# Peripheral.net
KiCad netlist of a schematic drawn in Altium Designer
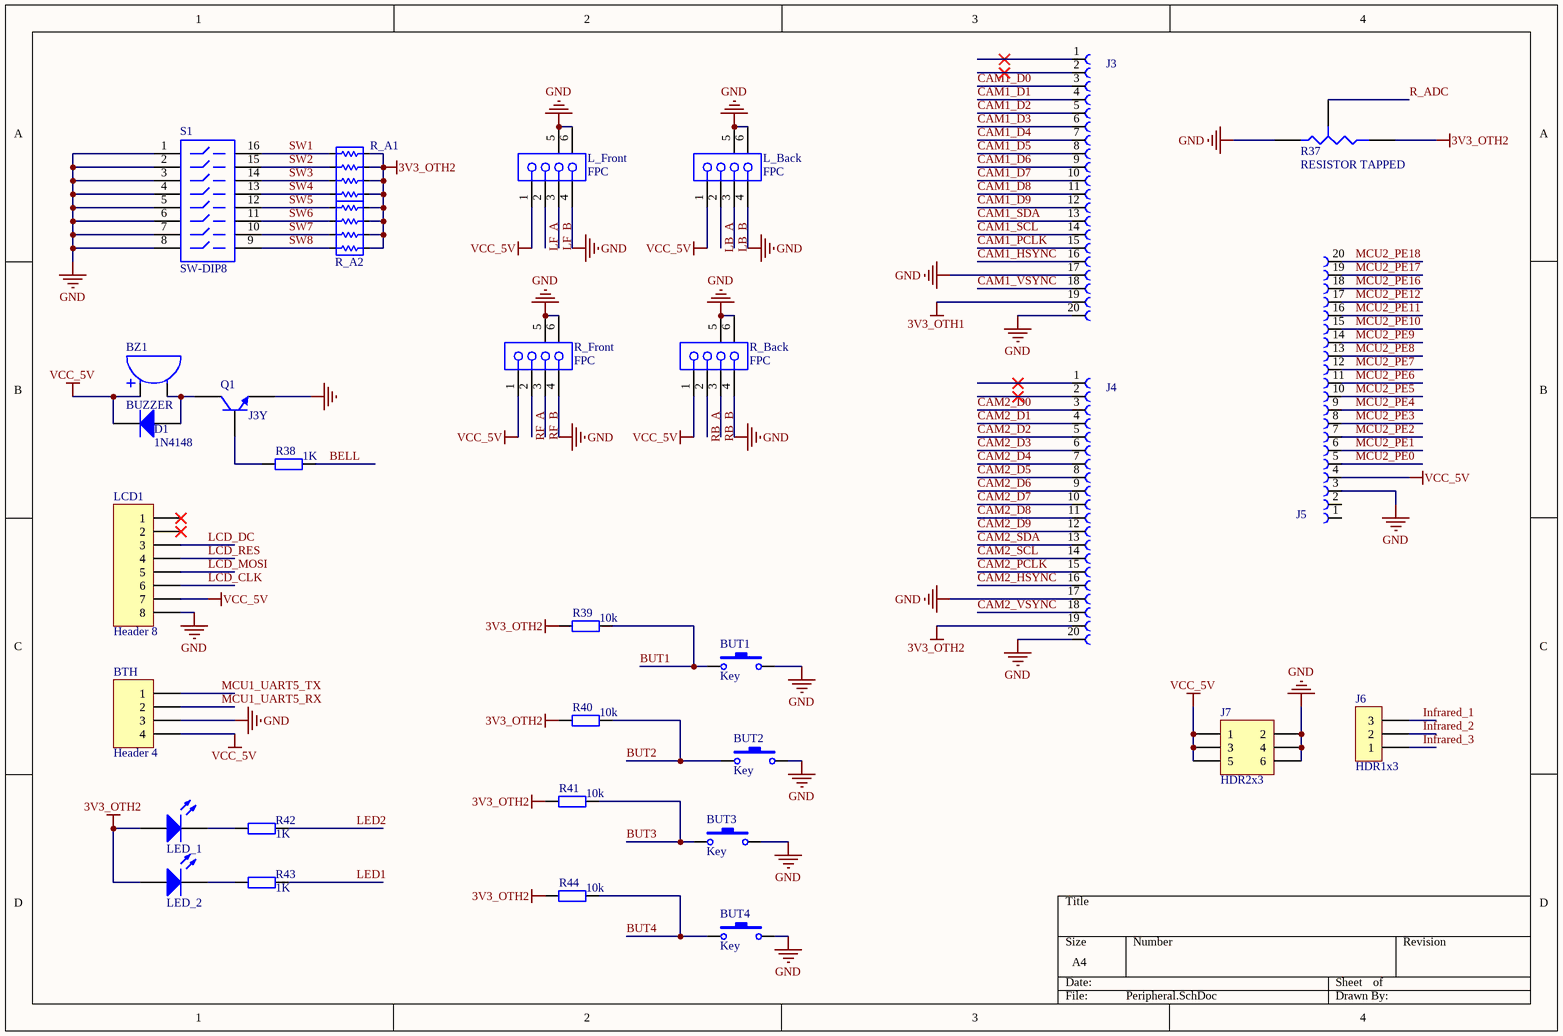
[diagram p0: Peripheral.SchDoc]

(export (version "E")
  (design (tool "Eeschema 10.0.6"))
  (components
    (comp (ref "BTH")
      (value "Header 4")
      (footprint "HDR1X4")
      (description "Header, 4-Pin")
      (fields (field (name "PUBLISHER") "Altium Limited"))
      (libsource (lib "K60_main board") (part "Header 4"))
    )
    (comp (ref "BUT1") (value "Key") (footprint "Key_PB") (libsource (lib "MKV58") (part "KEY")))
    (comp (ref "BUT2") (value "Key") (footprint "Key_PB") (libsource (lib "MKV58") (part "KEY")))
    (comp (ref "BUT3") (value "Key") (footprint "Key_PB") (libsource (lib "MKV58") (part "KEY")))
    (comp (ref "BUT4") (value "Key") (footprint "Key_PB") (libsource (lib "MKV58") (part "KEY")))
    (comp (ref "BZ1")
      (value "BUZZER")
      (footprint "BUZZER-D12.0X8.5-6.5-0.8")
      (description "Buzzer")
      (libsource (lib "MyLib") (part "BUZZER"))
    )
    (comp (ref "D1")
      (value "1N4148")
      (footprint "1N4148")
      (fields (field (name "PUBLISHER") "Altium Limited"))
      (libsource (lib "YMYPcbLib") (part "Diode"))
    )
    (comp (ref "J3")
      (value "~")
      (footprint "*68712014522")
      (description "WR-FPC 0.5mm ZIF Connector Bottom 20pin")
      (fields (field (name "MF") "Wurth Electronics") (field (name "MP") "68712014522"))
      (libsource (lib "MyLib") (part "FPC-0.5-20"))
    )
    (comp (ref "J4")
      (value "~")
      (footprint "*68712014522")
      (description "WR-FPC 0.5mm ZIF Connector Bottom 20pin")
      (fields (field (name "MF") "Wurth Electronics") (field (name "MP") "68712014522"))
      (libsource (lib "MyLib") (part "FPC-0.5-20"))
    )
    (comp (ref "J5")
      (value "68712014522")
      (footprint "*68712014522")
      (description "WR-FPC 0.5mm ZIF Connector Bottom 20pin")
      (fields (field (name "MF") "Wurth Electronics"))
      (libsource (lib "MyLib") (part "FPC-0.5-20"))
    )
    (comp (ref "J6")
      (value "HDR1x3")
      (footprint "PIN-3-2.54-1.0")
      (description "Connector")
      (libsource (lib "MyLib") (part "HDR1x3"))
    )
    (comp (ref "J7")
      (value "HDR2x3")
      (footprint "PIN-2x3-2.54-1.0")
      (description "Connector")
      (libsource (lib "MyLib") (part "HDR2x3"))
    )
    (comp (ref "LCD1")
      (value "Header 8")
      (footprint "HDR1X8")
      (description "Header, 8-Pin")
      (fields (field (name "PUBLISHER") "Altium Limited"))
      (libsource (lib "K60_main board") (part "Header 8"))
    )
    (comp (ref "LED_1") (value "LED") (footprint "LED") (libsource (lib "xunpianzhen") (part "LED")))
    (comp (ref "LED_2") (value "LED") (footprint "LED") (libsource (lib "xunpianzhen") (part "LED")))
    (comp (ref "L_Back")
      (value "FPC")
      (footprint "FH12-10(4)SA-1SH")
      (description "FH12 Series, \"Flip-Lock\" SMT/ZIF Connector - 1.0mm Spaced Bottom Eccentric Contact")
      (fields (field (name "PUBLISHER") "Altium Limited"))
      (libsource (lib "stub") (part "CL586-0537-0"))
    )
    (comp (ref "L_Front")
      (value "FPC")
      (footprint "FH12-10(4)SA-1SH")
      (description "FH12 Series, \"Flip-Lock\" SMT/ZIF Connector - 1.0mm Spaced Bottom Eccentric Contact")
      (fields (field (name "PUBLISHER") "Altium Limited"))
      (libsource (lib "stub") (part "CL586-0537-0"))
    )
    (comp (ref "Q1")
      (value "J3Y")
      (footprint "SOT23")
      (description "NPN Bipolar Transistor")
      (fields (field (name "PUBLISHER") "Altium Limited"))
      (libsource (lib "KL26_main board") (part "NPN"))
    )
    (comp (ref "R37")
      (value "RESISTOR TAPPED")
      (footprint "0932电位器")
      (libsource (lib "MyLib") (part "RESISTOR TAPPED"))
    )
    (comp (ref "R38")
      (value "1K")
      (footprint "0805")
      (description "Resistor")
      (fields (field (name "PUBLISHER") "Altium Limited"))
      (libsource (lib "Miscellaneous Devices") (part "Res2"))
    )
    (comp (ref "R39")
      (value "10k")
      (footprint "0805")
      (description "Resistor")
      (fields (field (name "Comment") "Res2") (field (name "PUBLISHER") "Altium Limited"))
      (libsource (lib "Miscellaneous Devices") (part "Res2"))
    )
    (comp (ref "R40")
      (value "10k")
      (footprint "0805")
      (description "Resistor")
      (fields (field (name "Comment") "Res2") (field (name "PUBLISHER") "Altium Limited"))
      (libsource (lib "Miscellaneous Devices") (part "Res2"))
    )
    (comp (ref "R41")
      (value "10k")
      (footprint "0805")
      (description "Resistor")
      (fields (field (name "Comment") "Res2") (field (name "PUBLISHER") "Altium Limited"))
      (libsource (lib "Miscellaneous Devices") (part "Res2"))
    )
    (comp (ref "R42")
      (value "1K")
      (footprint "0805")
      (description "Resistor")
      (fields (field (name "Comment") "Res2") (field (name "PUBLISHER") "Altium Limited"))
      (libsource (lib "Miscellaneous Devices") (part "Res2"))
    )
    (comp (ref "R43")
      (value "1K")
      (footprint "0805")
      (description "Resistor")
      (fields (field (name "Comment") "Res2") (field (name "PUBLISHER") "Altium Limited"))
      (libsource (lib "Miscellaneous Devices") (part "Res2"))
    )
    (comp (ref "R44")
      (value "10k")
      (footprint "0805")
      (description "Resistor")
      (fields (field (name "Comment") "Res2") (field (name "PUBLISHER") "Altium Limited"))
      (libsource (lib "Miscellaneous Devices") (part "Res2"))
    )
    (comp (ref "R_A1") (value "Res Array") (footprint "R_Array") (libsource (lib "MyLib") (part "R_Array")))
    (comp (ref "R_A2")
      (value "Resistor Array")
      (footprint "Res Array")
      (description "Resistor")
      (fields (field (name "PUBLISHER") "Altium Limited"))
      (libsource (lib "MyLib") (part "Res_Array_4"))
    )
    (comp (ref "R_Back")
      (value "FPC")
      (footprint "FH12-10(4)SA-1SH")
      (description "FH12 Series, \"Flip-Lock\" SMT/ZIF Connector - 1.0mm Spaced Bottom Eccentric Contact")
      (fields (field (name "PUBLISHER") "Altium Limited"))
      (libsource (lib "stub") (part "CL586-0537-0"))
    )
    (comp (ref "R_Front")
      (value "FPC")
      (footprint "FH12-10(4)SA-1SH")
      (description "FH12 Series, \"Flip-Lock\" SMT/ZIF Connector - 1.0mm Spaced Bottom Eccentric Contact")
      (fields (field (name "PUBLISHER") "Altium Limited"))
      (libsource (lib "stub") (part "CL586-0537-0"))
    )
    (comp (ref "S1")
      (value "SW-DIP8")
      (footprint "DIP-16-KEY")
      (description "4009 Series DIP Switch, Raised actuator")
      (fields (field (name "PUBLISHER") "Altium Limited"))
      (libsource (lib "Miscellaneous Devices") (part "SW-DIP8"))
    )
  )
  (nets
    (net (code "1") (name "/BELL") (class "Default")
      (node (ref "R38") (pin "2") (pinfunction "2_2") (pintype "passive"))
    )
    (net (code "2") (name "/BUT1") (class "Default")
      (node (ref "BUT1") (pin "1") (pinfunction "1_1") (pintype "passive"))
      (node (ref "R39") (pin "2") (pinfunction "2_2") (pintype "passive"))
    )
    (net (code "3") (name "/BUT2") (class "Default")
      (node (ref "BUT2") (pin "1") (pinfunction "1_1") (pintype "passive"))
      (node (ref "R40") (pin "2") (pinfunction "2_2") (pintype "passive"))
    )
    (net (code "4") (name "/BUT3") (class "Default")
      (node (ref "BUT3") (pin "1") (pinfunction "1_1") (pintype "passive"))
      (node (ref "R41") (pin "2") (pinfunction "2_2") (pintype "passive"))
    )
    (net (code "5") (name "/BUT4") (class "Default")
      (node (ref "BUT4") (pin "1") (pinfunction "1_1") (pintype "passive"))
      (node (ref "R44") (pin "2") (pinfunction "2_2") (pintype "passive"))
    )
    (net (code "6") (name "/CAM1_D0") (class "Default")
      (node (ref "J3") (pin "3") (pinfunction "3_3") (pintype "passive"))
    )
    (net (code "7") (name "/CAM1_D1") (class "Default")
      (node (ref "J3") (pin "4") (pinfunction "4_4") (pintype "passive"))
    )
    (net (code "8") (name "/CAM1_D2") (class "Default")
      (node (ref "J3") (pin "5") (pinfunction "5_5") (pintype "passive"))
    )
    (net (code "9") (name "/CAM1_D3") (class "Default")
      (node (ref "J3") (pin "6") (pinfunction "6_6") (pintype "passive"))
    )
    (net (code "10") (name "/CAM1_D4") (class "Default")
      (node (ref "J3") (pin "7") (pinfunction "7_7") (pintype "passive"))
    )
    (net (code "11") (name "/CAM1_D5") (class "Default")
      (node (ref "J3") (pin "8") (pinfunction "8_8") (pintype "passive"))
    )
    (net (code "12") (name "/CAM1_D6") (class "Default")
      (node (ref "J3") (pin "9") (pinfunction "9_9") (pintype "passive"))
    )
    (net (code "13") (name "/CAM1_D7") (class "Default")
      (node (ref "J3") (pin "10") (pinfunction "10_10") (pintype "passive"))
    )
    (net (code "14") (name "/CAM1_D8") (class "Default")
      (node (ref "J3") (pin "11") (pinfunction "11_11") (pintype "passive"))
    )
    (net (code "15") (name "/CAM1_D9") (class "Default")
      (node (ref "J3") (pin "12") (pinfunction "12_12") (pintype "passive"))
    )
    (net (code "16") (name "/CAM1_HSYNC") (class "Default")
      (node (ref "J3") (pin "16") (pinfunction "16_16") (pintype "passive"))
    )
    (net (code "17") (name "/CAM1_PCLK") (class "Default")
      (node (ref "J3") (pin "15") (pinfunction "15_15") (pintype "passive"))
    )
    (net (code "18") (name "/CAM1_SCL") (class "Default")
      (node (ref "J3") (pin "14") (pinfunction "14_14") (pintype "passive"))
    )
    (net (code "19") (name "/CAM1_SDA") (class "Default")
      (node (ref "J3") (pin "13") (pinfunction "13_13") (pintype "passive"))
    )
    (net (code "20") (name "/CAM1_VSYNC") (class "Default")
      (node (ref "J3") (pin "18") (pinfunction "18_18") (pintype "passive"))
    )
    (net (code "21") (name "/CAM2_D0") (class "Default")
      (node (ref "J4") (pin "3") (pinfunction "3_3") (pintype "passive"))
    )
    (net (code "22") (name "/CAM2_D1") (class "Default")
      (node (ref "J4") (pin "4") (pinfunction "4_4") (pintype "passive"))
    )
    (net (code "23") (name "/CAM2_D2") (class "Default")
      (node (ref "J4") (pin "5") (pinfunction "5_5") (pintype "passive"))
    )
    (net (code "24") (name "/CAM2_D3") (class "Default")
      (node (ref "J4") (pin "6") (pinfunction "6_6") (pintype "passive"))
    )
    (net (code "25") (name "/CAM2_D4") (class "Default")
      (node (ref "J4") (pin "7") (pinfunction "7_7") (pintype "passive"))
    )
    (net (code "26") (name "/CAM2_D5") (class "Default")
      (node (ref "J4") (pin "8") (pinfunction "8_8") (pintype "passive"))
    )
    (net (code "27") (name "/CAM2_D6") (class "Default")
      (node (ref "J4") (pin "9") (pinfunction "9_9") (pintype "passive"))
    )
    (net (code "28") (name "/CAM2_D7") (class "Default")
      (node (ref "J4") (pin "10") (pinfunction "10_10") (pintype "passive"))
    )
    (net (code "29") (name "/CAM2_D8") (class "Default")
      (node (ref "J4") (pin "11") (pinfunction "11_11") (pintype "passive"))
    )
    (net (code "30") (name "/CAM2_D9") (class "Default")
      (node (ref "J4") (pin "12") (pinfunction "12_12") (pintype "passive"))
    )
    (net (code "31") (name "/CAM2_HSYNC") (class "Default")
      (node (ref "J4") (pin "16") (pinfunction "16_16") (pintype "passive"))
    )
    (net (code "32") (name "/CAM2_PCLK") (class "Default")
      (node (ref "J4") (pin "15") (pinfunction "15_15") (pintype "passive"))
    )
    (net (code "33") (name "/CAM2_SCL") (class "Default")
      (node (ref "J4") (pin "14") (pinfunction "14_14") (pintype "passive"))
    )
    (net (code "34") (name "/CAM2_SDA") (class "Default")
      (node (ref "J4") (pin "13") (pinfunction "13_13") (pintype "passive"))
    )
    (net (code "35") (name "/CAM2_VSYNC") (class "Default")
      (node (ref "J4") (pin "18") (pinfunction "18_18") (pintype "passive"))
    )
    (net (code "36") (name "/Infrared_1") (class "Default")
      (node (ref "J6") (pin "3") (pinfunction "3_3") (pintype "passive"))
    )
    (net (code "37") (name "/Infrared_2") (class "Default")
      (node (ref "J6") (pin "2") (pinfunction "2_2") (pintype "passive"))
    )
    (net (code "38") (name "/Infrared_3") (class "Default")
      (node (ref "J6") (pin "1") (pinfunction "1_1") (pintype "passive"))
    )
    (net (code "39") (name "/LB_A") (class "Default")
      (node (ref "L_Back") (pin "2") (pinfunction "2_2") (pintype "passive"))
    )
    (net (code "40") (name "/LB_B") (class "Default")
      (node (ref "L_Back") (pin "3") (pinfunction "3_3") (pintype "passive"))
    )
    (net (code "41") (name "/LCD_CLK") (class "Default")
      (node (ref "LCD1") (pin "6") (pinfunction "6_6") (pintype "passive"))
    )
    (net (code "42") (name "/LCD_DC") (class "Default")
      (node (ref "LCD1") (pin "3") (pinfunction "3_3") (pintype "passive"))
    )
    (net (code "43") (name "/LCD_MOSI") (class "Default")
      (node (ref "LCD1") (pin "5") (pinfunction "5_5") (pintype "passive"))
    )
    (net (code "44") (name "/LCD_RES") (class "Default")
      (node (ref "LCD1") (pin "4") (pinfunction "4_4") (pintype "passive"))
    )
    (net (code "45") (name "/LED1") (class "Default")
      (node (ref "R43") (pin "2") (pinfunction "2_2") (pintype "passive"))
    )
    (net (code "46") (name "/LED2") (class "Default")
      (node (ref "R42") (pin "2") (pinfunction "2_2") (pintype "passive"))
    )
    (net (code "47") (name "/LF_A") (class "Default")
      (node (ref "L_Front") (pin "2") (pinfunction "2_2") (pintype "passive"))
    )
    (net (code "48") (name "/LF_B") (class "Default")
      (node (ref "L_Front") (pin "3") (pinfunction "3_3") (pintype "passive"))
    )
    (net (code "49") (name "/MCU1_UART5_RX") (class "Default")
      (node (ref "BTH") (pin "2") (pinfunction "2_2") (pintype "passive"))
    )
    (net (code "50") (name "/MCU1_UART5_TX") (class "Default")
      (node (ref "BTH") (pin "1") (pinfunction "1_1") (pintype "passive"))
    )
    (net (code "51") (name "/MCU2_PE0") (class "Default")
      (node (ref "J5") (pin "5") (pinfunction "5_5") (pintype "passive"))
    )
    (net (code "52") (name "/MCU2_PE1") (class "Default")
      (node (ref "J5") (pin "6") (pinfunction "6_6") (pintype "passive"))
    )
    (net (code "53") (name "/MCU2_PE2") (class "Default")
      (node (ref "J5") (pin "7") (pinfunction "7_7") (pintype "passive"))
    )
    (net (code "54") (name "/MCU2_PE3") (class "Default")
      (node (ref "J5") (pin "8") (pinfunction "8_8") (pintype "passive"))
    )
    (net (code "55") (name "/MCU2_PE4") (class "Default")
      (node (ref "J5") (pin "9") (pinfunction "9_9") (pintype "passive"))
    )
    (net (code "56") (name "/MCU2_PE5") (class "Default")
      (node (ref "J5") (pin "10") (pinfunction "10_10") (pintype "passive"))
    )
    (net (code "57") (name "/MCU2_PE6") (class "Default")
      (node (ref "J5") (pin "11") (pinfunction "11_11") (pintype "passive"))
    )
    (net (code "58") (name "/MCU2_PE7") (class "Default")
      (node (ref "J5") (pin "12") (pinfunction "12_12") (pintype "passive"))
    )
    (net (code "59") (name "/MCU2_PE8") (class "Default")
      (node (ref "J5") (pin "13") (pinfunction "13_13") (pintype "passive"))
    )
    (net (code "60") (name "/MCU2_PE9") (class "Default")
      (node (ref "J5") (pin "14") (pinfunction "14_14") (pintype "passive"))
    )
    (net (code "61") (name "/MCU2_PE10") (class "Default")
      (node (ref "J5") (pin "15") (pinfunction "15_15") (pintype "passive"))
    )
    (net (code "62") (name "/MCU2_PE11") (class "Default")
      (node (ref "J5") (pin "16") (pinfunction "16_16") (pintype "passive"))
    )
    (net (code "63") (name "/MCU2_PE12") (class "Default")
      (node (ref "J5") (pin "17") (pinfunction "17_17") (pintype "passive"))
    )
    (net (code "64") (name "/MCU2_PE16") (class "Default")
      (node (ref "J5") (pin "18") (pinfunction "18_18") (pintype "passive"))
    )
    (net (code "65") (name "/MCU2_PE17") (class "Default")
      (node (ref "J5") (pin "19") (pinfunction "19_19") (pintype "passive"))
    )
    (net (code "66") (name "/MCU2_PE18") (class "Default")
      (node (ref "J5") (pin "20") (pinfunction "20_20") (pintype "passive"))
    )
    (net (code "67") (name "/RB_A") (class "Default")
      (node (ref "R_Back") (pin "2") (pinfunction "2_2") (pintype "passive"))
    )
    (net (code "68") (name "/RB_B") (class "Default")
      (node (ref "R_Back") (pin "3") (pinfunction "3_3") (pintype "passive"))
    )
    (net (code "69") (name "/RF_A") (class "Default")
      (node (ref "R_Front") (pin "2") (pinfunction "2_2") (pintype "passive"))
    )
    (net (code "70") (name "/RF_B") (class "Default")
      (node (ref "R_Front") (pin "3") (pinfunction "3_3") (pintype "passive"))
    )
    (net (code "71") (name "/R_ADC") (class "Default")
      (node (ref "R37") (pin "3") (pinfunction "TAP_3") (pintype "passive"))
    )
    (net (code "72") (name "/SW1") (class "Default")
      (node (ref "R_A1") (pin "1") (pinfunction "1_1") (pintype "passive"))
      (node (ref "S1") (pin "16") (pinfunction "16_16") (pintype "passive"))
    )
    (net (code "73") (name "/SW2") (class "Default")
      (node (ref "R_A1") (pin "2") (pinfunction "2_2") (pintype "passive"))
      (node (ref "S1") (pin "15") (pinfunction "15_15") (pintype "passive"))
    )
    (net (code "74") (name "/SW3") (class "Default")
      (node (ref "R_A1") (pin "3") (pinfunction "3_3") (pintype "passive"))
      (node (ref "S1") (pin "14") (pinfunction "14_14") (pintype "passive"))
    )
    (net (code "75") (name "/SW4") (class "Default")
      (node (ref "R_A1") (pin "4") (pinfunction "4_4") (pintype "passive"))
      (node (ref "S1") (pin "13") (pinfunction "13_13") (pintype "passive"))
    )
    (net (code "76") (name "/SW5") (class "Default")
      (node (ref "R_A2") (pin "1") (pinfunction "1_1") (pintype "passive"))
      (node (ref "S1") (pin "12") (pinfunction "12_12") (pintype "passive"))
    )
    (net (code "77") (name "/SW6") (class "Default")
      (node (ref "R_A2") (pin "2") (pinfunction "2_2") (pintype "passive"))
      (node (ref "S1") (pin "11") (pinfunction "11_11") (pintype "passive"))
    )
    (net (code "78") (name "/SW7") (class "Default")
      (node (ref "R_A2") (pin "3") (pinfunction "3_3") (pintype "passive"))
      (node (ref "S1") (pin "10") (pinfunction "10_10") (pintype "passive"))
    )
    (net (code "79") (name "/SW8") (class "Default")
      (node (ref "R_A2") (pin "4") (pinfunction "4_4") (pintype "passive"))
      (node (ref "S1") (pin "9") (pinfunction "9_9") (pintype "passive"))
    )
    (net (code "80") (name "3V3_OTH1") (class "Default")
      (node (ref "J3") (pin "19") (pinfunction "19_19") (pintype "passive"))
    )
    (net (code "81") (name "3V3_OTH2") (class "Default")
      (node (ref "J4") (pin "19") (pinfunction "19_19") (pintype "passive"))
      (node (ref "LED_1") (pin "1") (pinfunction "A_1") (pintype "passive"))
      (node (ref "LED_2") (pin "1") (pinfunction "A_1") (pintype "passive"))
      (node (ref "R37") (pin "2") (pinfunction "B_2") (pintype "passive"))
      (node (ref "R39") (pin "1") (pinfunction "1_1") (pintype "passive"))
      (node (ref "R40") (pin "1") (pinfunction "1_1") (pintype "passive"))
      (node (ref "R41") (pin "1") (pinfunction "1_1") (pintype "passive"))
      (node (ref "R44") (pin "1") (pinfunction "1_1") (pintype "passive"))
      (node (ref "R_A1") (pin "5") (pinfunction "5_5") (pintype "passive"))
      (node (ref "R_A1") (pin "6") (pinfunction "6_6") (pintype "passive"))
      (node (ref "R_A1") (pin "7") (pinfunction "7_7") (pintype "passive"))
      (node (ref "R_A1") (pin "8") (pinfunction "8_8") (pintype "passive"))
      (node (ref "R_A2") (pin "5") (pinfunction "5_5") (pintype "passive"))
      (node (ref "R_A2") (pin "6") (pinfunction "6_6") (pintype "passive"))
      (node (ref "R_A2") (pin "7") (pinfunction "7_7") (pintype "passive"))
      (node (ref "R_A2") (pin "8") (pinfunction "8_8") (pintype "passive"))
    )
    (net (code "82") (name "GND") (class "Default")
      (node (ref "BTH") (pin "3") (pinfunction "3_3") (pintype "passive"))
      (node (ref "BUT1") (pin "2") (pinfunction "2_2") (pintype "passive"))
      (node (ref "BUT2") (pin "2") (pinfunction "2_2") (pintype "passive"))
      (node (ref "BUT3") (pin "2") (pinfunction "2_2") (pintype "passive"))
      (node (ref "BUT4") (pin "2") (pinfunction "2_2") (pintype "passive"))
      (node (ref "J3") (pin "17") (pinfunction "17_17") (pintype "passive"))
      (node (ref "J3") (pin "20") (pinfunction "20_20") (pintype "passive"))
      (node (ref "J4") (pin "17") (pinfunction "17_17") (pintype "passive"))
      (node (ref "J4") (pin "20") (pinfunction "20_20") (pintype "passive"))
      (node (ref "J5") (pin "3") (pinfunction "3_3") (pintype "passive"))
      (node (ref "J7") (pin "2") (pinfunction "2_2") (pintype "passive"))
      (node (ref "J7") (pin "4") (pinfunction "4_4") (pintype "passive"))
      (node (ref "J7") (pin "6") (pinfunction "6_6") (pintype "passive"))
      (node (ref "LCD1") (pin "8") (pinfunction "8_8") (pintype "passive"))
      (node (ref "L_Back") (pin "4") (pinfunction "4_4") (pintype "passive"))
      (node (ref "L_Back") (pin "5") (pinfunction "MH1_5") (pintype "passive"))
      (node (ref "L_Back") (pin "6") (pinfunction "MH2_6") (pintype "passive"))
      (node (ref "L_Front") (pin "4") (pinfunction "4_4") (pintype "passive"))
      (node (ref "L_Front") (pin "5") (pinfunction "MH1_5") (pintype "passive"))
      (node (ref "L_Front") (pin "6") (pinfunction "MH2_6") (pintype "passive"))
      (node (ref "Q1") (pin "3") (pinfunction "E_3") (pintype "passive"))
      (node (ref "R37") (pin "1") (pinfunction "A_1") (pintype "passive"))
      (node (ref "R_Back") (pin "4") (pinfunction "4_4") (pintype "passive"))
      (node (ref "R_Back") (pin "5") (pinfunction "MH1_5") (pintype "passive"))
      (node (ref "R_Back") (pin "6") (pinfunction "MH2_6") (pintype "passive"))
      (node (ref "R_Front") (pin "4") (pinfunction "4_4") (pintype "passive"))
      (node (ref "R_Front") (pin "5") (pinfunction "MH1_5") (pintype "passive"))
      (node (ref "R_Front") (pin "6") (pinfunction "MH2_6") (pintype "passive"))
      (node (ref "S1") (pin "1") (pinfunction "1_1") (pintype "passive"))
      (node (ref "S1") (pin "2") (pinfunction "2_2") (pintype "passive"))
      (node (ref "S1") (pin "3") (pinfunction "3_3") (pintype "passive"))
      (node (ref "S1") (pin "4") (pinfunction "4_4") (pintype "passive"))
      (node (ref "S1") (pin "5") (pinfunction "5_5") (pintype "passive"))
      (node (ref "S1") (pin "6") (pinfunction "6_6") (pintype "passive"))
      (node (ref "S1") (pin "7") (pinfunction "7_7") (pintype "passive"))
      (node (ref "S1") (pin "8") (pinfunction "8_8") (pintype "passive"))
    )
    (net (code "83") (name "Net-(D1-A)") (class "Default")
      (node (ref "BZ1") (pin "2") (pinfunction "2_2") (pintype "passive"))
      (node (ref "D1") (pin "1") (pinfunction "A_1") (pintype "passive"))
      (node (ref "Q1") (pin "1") (pinfunction "C_1") (pintype "passive"))
    )
    (net (code "84") (name "Net-(LED_1-K)") (class "Default")
      (node (ref "LED_1") (pin "2") (pinfunction "K_2") (pintype "passive"))
      (node (ref "R42") (pin "1") (pinfunction "1_1") (pintype "passive"))
    )
    (net (code "85") (name "Net-(LED_2-K)") (class "Default")
      (node (ref "LED_2") (pin "2") (pinfunction "K_2") (pintype "passive"))
      (node (ref "R43") (pin "1") (pinfunction "1_1") (pintype "passive"))
    )
    (net (code "86") (name "Net-(Q1-B)") (class "Default")
      (node (ref "Q1") (pin "2") (pinfunction "B_2") (pintype "passive"))
      (node (ref "R38") (pin "1") (pinfunction "1_1") (pintype "passive"))
    )
    (net (code "87") (name "VCC_5V") (class "Default")
      (node (ref "BTH") (pin "4") (pinfunction "4_4") (pintype "passive"))
      (node (ref "BZ1") (pin "1") (pinfunction "1_1") (pintype "passive"))
      (node (ref "D1") (pin "2") (pinfunction "K_2") (pintype "passive"))
      (node (ref "J5") (pin "4") (pinfunction "4_4") (pintype "passive"))
      (node (ref "J7") (pin "1") (pinfunction "1_1") (pintype "passive"))
      (node (ref "J7") (pin "3") (pinfunction "3_3") (pintype "passive"))
      (node (ref "J7") (pin "5") (pinfunction "5_5") (pintype "passive"))
      (node (ref "LCD1") (pin "7") (pinfunction "7_7") (pintype "passive"))
      (node (ref "L_Back") (pin "1") (pinfunction "1_1") (pintype "passive"))
      (node (ref "L_Front") (pin "1") (pinfunction "1_1") (pintype "passive"))
      (node (ref "R_Back") (pin "1") (pinfunction "1_1") (pintype "passive"))
      (node (ref "R_Front") (pin "1") (pinfunction "1_1") (pintype "passive"))
    )
    (net (code "88") (name "unconnected-(J3-Pad1)") (class "Default")
      (node (ref "J3") (pin "1") (pinfunction "1_1") (pintype "passive"))
    )
    (net (code "89") (name "unconnected-(J3-Pad2)") (class "Default")
      (node (ref "J3") (pin "2") (pinfunction "2_2") (pintype "passive"))
    )
    (net (code "90") (name "unconnected-(J4-Pad1)") (class "Default")
      (node (ref "J4") (pin "1") (pinfunction "1_1") (pintype "passive"))
    )
    (net (code "91") (name "unconnected-(J4-Pad2)") (class "Default")
      (node (ref "J4") (pin "2") (pinfunction "2_2") (pintype "passive"))
    )
    (net (code "92") (name "unconnected-(J5-Pad1)") (class "Default")
      (node (ref "J5") (pin "1") (pinfunction "1_1") (pintype "passive"))
    )
    (net (code "93") (name "unconnected-(J5-Pad2)") (class "Default")
      (node (ref "J5") (pin "2") (pinfunction "2_2") (pintype "passive"))
    )
    (net (code "94") (name "unconnected-(LCD1-Pad1)") (class "Default")
      (node (ref "LCD1") (pin "1") (pinfunction "1_1") (pintype "passive+no_connect"))
    )
    (net (code "95") (name "unconnected-(LCD1-Pad2)") (class "Default")
      (node (ref "LCD1") (pin "2") (pinfunction "2_2") (pintype "passive+no_connect"))
    )
  )
)
